# MastModule.net
KiCad netlist of a schematic drawn in EAGLE
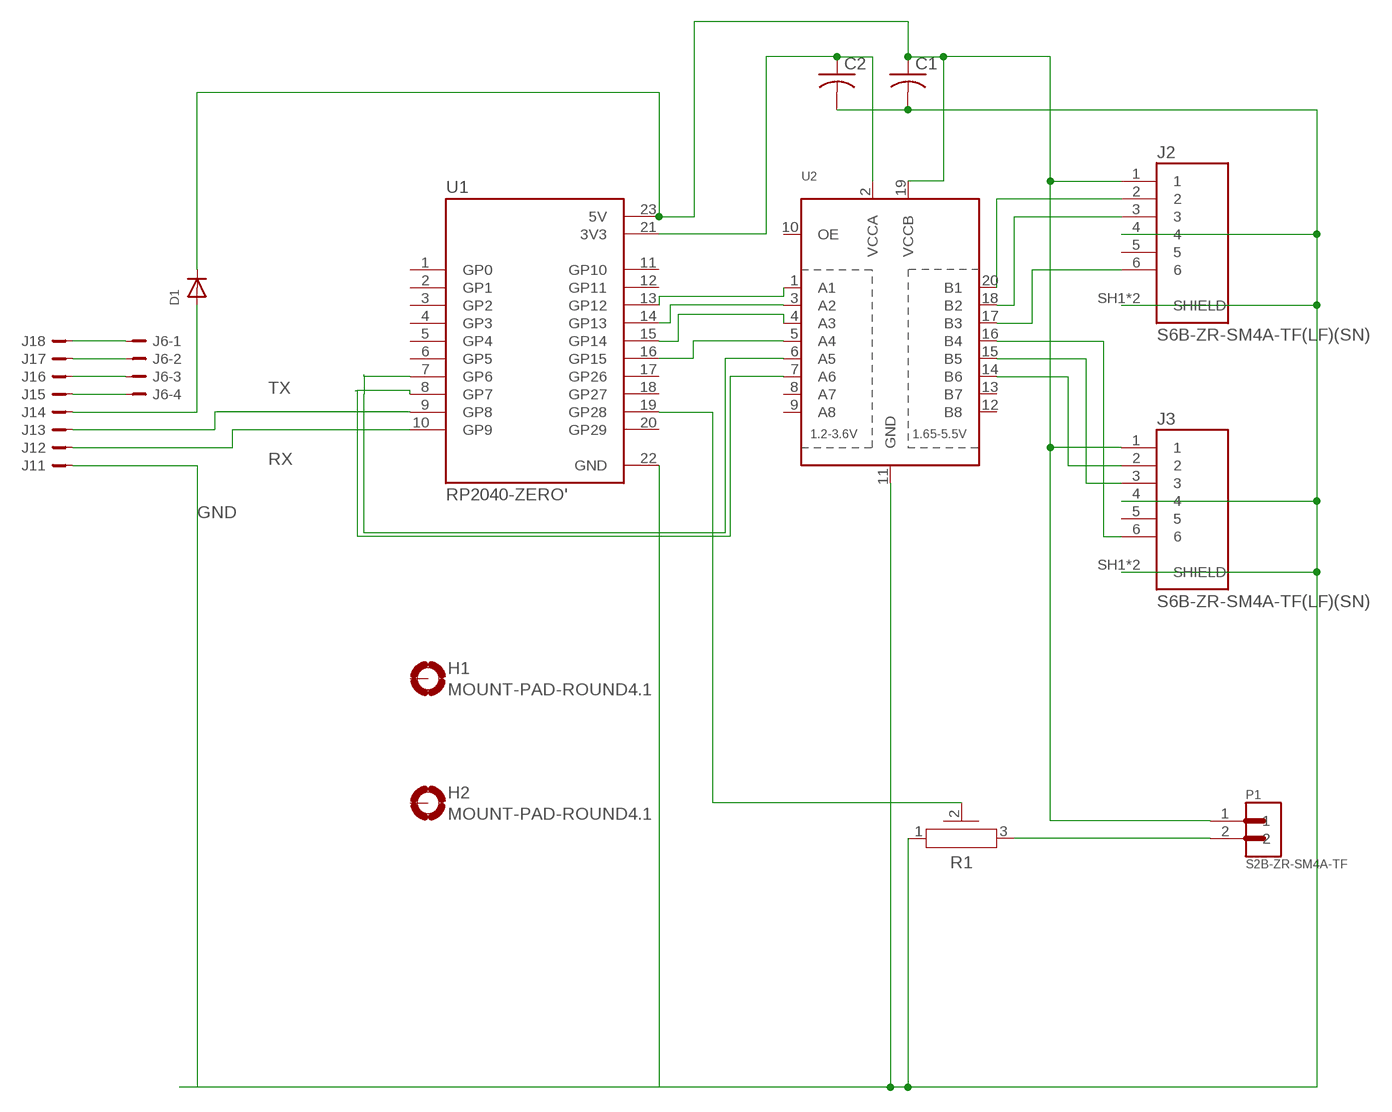
[diagram p0: schematic, sheet 1]

(export (version "E")
  (design (tool "Eeschema 10.0.6"))
  (components
    (comp (ref "C1")
      (value "C-USC1210")
      (footprint "eagle-import:C1210")
      (libsource (lib "eagle-import") (part "C-USC1210"))
    )
    (comp (ref "C2")
      (value "C-USC1210")
      (footprint "eagle-import:C1210")
      (libsource (lib "eagle-import") (part "C-USC1210"))
    )
    (comp (ref "D1")
      (value "DIODESMA")
      (footprint "eagle-import:SMADIODE")
      (libsource (lib "eagle-import") (part "DIODESMA"))
    )
    (comp (ref "H1")
      (value "MOUNT-PAD-ROUND4.1")
      (footprint "eagle-import:4,1-PAD")
      (libsource (lib "eagle-import") (part "MOUNT-PAD-ROUND4.1"))
    )
    (comp (ref "H2")
      (value "MOUNT-PAD-ROUND4.1")
      (footprint "eagle-import:4,1-PAD")
      (libsource (lib "eagle-import") (part "MOUNT-PAD-ROUND4.1"))
    )
    (comp (ref "J1")
      (value "B8B-PH-K-S")
      (footprint "eagle-import:B8B-PH-K-S")
      (libsource (lib "eagle-import") (part "B8B-PH-K-S"))
    )
    (comp (ref "J2")
      (value "S6B-ZR-SM4A-TF(LF)(SN)")
      (footprint "eagle-import:JST_S6B-ZR-SM4A-TF(LF)(SN)")
      (fields (field (name "MF") "JST Sales America Inc."))
      (libsource (lib "eagle-import") (part "S6B-ZR-SM4A-TF(LF)(SN)"))
    )
    (comp (ref "J3")
      (value "S6B-ZR-SM4A-TF(LF)(SN)")
      (footprint "eagle-import:JST_S6B-ZR-SM4A-TF(LF)(SN)")
      (fields (field (name "MF") "JST Sales America Inc."))
      (libsource (lib "eagle-import") (part "S6B-ZR-SM4A-TF(LF)(SN)"))
    )
    (comp (ref "J6")
      (value "JST-PH-4_TH-RA")
      (footprint "eagle-import:S4B-PH-KL")
      (fields (field (name "MF") "JST") (field (name "MPN") "S4B-PH-KL"))
      (libsource (lib "eagle-import") (part "JST-PH-4_TH-RA"))
    )
    (comp (ref "P1")
      (value "S2B-ZR-SM4A-TF")
      (footprint "eagle-import:JST_S2B-ZR-SM4A-TF")
      (fields (field (name "MF") "JST Sales"))
      (libsource (lib "eagle-import") (part "S2B-ZR-SM4A-TF"))
    )
    (comp (ref "R1")
      (value "PV36X")
      (footprint "eagle-import:PV36X")
      (fields
        (field (name "MANUFACTURER") "Bourns Inc.")
        (field (name "MPN") "PV36Xx")
        (field (name "TOLERANCE") "±10%")
      )
      (libsource (lib "eagle-import") (part "PV36X"))
    )
    (comp (ref "U1")
      (value "RP2040-ZERO'")
      (footprint "eagle-import:MODULE_RP2040-ZERO")
      (fields (field (name "MF") "Waveshare Electronics") (field (name "MP") "RP2040-ZERO"))
      (libsource (lib "eagle-import") (part "RP2040-ZERO'"))
    )
    (comp (ref "U2")
      (value "TXB0108PWR")
      (footprint "eagle-import:TSSOP20")
      (libsource (lib "eagle-import") (part "TXB0108PWR"))
    )
  )
  (nets
    (net (code "1") (name "/GND") (class "Default")
      (node (ref "C1") (pin "2") (pinfunction "2_2") (pintype "passive"))
      (node (ref "C2") (pin "2") (pinfunction "2_2") (pintype "passive"))
      (node (ref "J1") (pin "1") (pinfunction "1_1") (pintype "passive"))
      (node (ref "J2") (pin "4") (pinfunction "4_4") (pintype "passive"))
      (node (ref "J2") (pin "SH1") (pinfunction "SHIELD_SH1") (pintype "passive"))
      (node (ref "J2") (pin "SH2") (pinfunction "SHIELD_SH2") (pintype "passive"))
      (node (ref "J3") (pin "4") (pinfunction "4_4") (pintype "passive"))
      (node (ref "J3") (pin "SH1") (pinfunction "SHIELD_SH1") (pintype "passive"))
      (node (ref "J3") (pin "SH2") (pinfunction "SHIELD_SH2") (pintype "passive"))
      (node (ref "R1") (pin "1") (pinfunction "P$1_1") (pintype "passive"))
      (node (ref "U1") (pin "22") (pinfunction "GND_22") (pintype "power_in"))
      (node (ref "U2") (pin "11") (pinfunction "GND_11") (pintype "bidirectional"))
    )
    (net (code "2") (name "/RX") (class "Default")
      (node (ref "J1") (pin "2") (pinfunction "1_2") (pintype "passive"))
      (node (ref "U1") (pin "10") (pinfunction "GP9_10") (pintype "bidirectional"))
    )
    (net (code "3") (name "/TX") (class "Default")
      (node (ref "J1") (pin "3") (pinfunction "1_3") (pintype "passive"))
      (node (ref "U1") (pin "9") (pinfunction "GP8_9") (pintype "bidirectional"))
    )
    (net (code "4") (name "Net-(J1D-1)") (class "Default")
      (node (ref "D1") (pin "A") (pinfunction "A_A") (pintype "passive"))
      (node (ref "J1") (pin "4") (pinfunction "1_4") (pintype "passive"))
    )
    (net (code "5") (name "Net-(J1E-1)") (class "Default")
      (node (ref "J1") (pin "5") (pinfunction "1_5") (pintype "passive"))
      (node (ref "J6") (pin "4") (pinfunction "1_4") (pintype "passive"))
    )
    (net (code "6") (name "Net-(J1F-1)") (class "Default")
      (node (ref "J1") (pin "6") (pinfunction "1_6") (pintype "passive"))
      (node (ref "J6") (pin "3") (pinfunction "1_3") (pintype "passive"))
    )
    (net (code "7") (name "Net-(J1G-1)") (class "Default")
      (node (ref "J1") (pin "7") (pinfunction "1_7") (pintype "passive"))
      (node (ref "J6") (pin "2") (pinfunction "1_2") (pintype "passive"))
    )
    (net (code "8") (name "Net-(J1H-1)") (class "Default")
      (node (ref "J1") (pin "8") (pinfunction "1_8") (pintype "passive"))
      (node (ref "J6") (pin "1") (pinfunction "1_1") (pintype "passive"))
    )
    (net (code "9") (name "Net-(R1-P$2)") (class "Default")
      (node (ref "R1") (pin "2") (pinfunction "P$2_2") (pintype "passive"))
      (node (ref "U1") (pin "19") (pinfunction "GP28_19") (pintype "bidirectional"))
    )
    (net (code "10") (name "Net-(R1-P$3)") (class "Default")
      (node (ref "P1") (pin "2") (pinfunction "2_2") (pintype "passive"))
      (node (ref "R1") (pin "3") (pinfunction "P$3_3") (pintype "passive"))
    )
    (net (code "11") (name "Net-(U1-3V3)") (class "Default")
      (node (ref "C2") (pin "1") (pinfunction "1_1") (pintype "passive"))
      (node (ref "U1") (pin "21") (pinfunction "3V3_21") (pintype "power_in"))
      (node (ref "U2") (pin "2") (pinfunction "VCCA_2") (pintype "bidirectional"))
    )
    (net (code "12") (name "Net-(U1-5V)") (class "Default")
      (node (ref "C1") (pin "1") (pinfunction "1_1") (pintype "passive"))
      (node (ref "D1") (pin "C") (pinfunction "C_C") (pintype "passive"))
      (node (ref "J2") (pin "1") (pinfunction "1_1") (pintype "passive"))
      (node (ref "J3") (pin "1") (pinfunction "1_1") (pintype "passive"))
      (node (ref "P1") (pin "1") (pinfunction "1_1") (pintype "passive"))
      (node (ref "U1") (pin "23") (pinfunction "5V_23") (pintype "power_in"))
      (node (ref "U2") (pin "19") (pinfunction "VCCB_19") (pintype "bidirectional"))
    )
    (net (code "13") (name "Net-(U1-GP6)") (class "Default")
      (node (ref "U1") (pin "7") (pinfunction "GP6_7") (pintype "bidirectional"))
      (node (ref "U2") (pin "6") (pinfunction "A5_6") (pintype "bidirectional"))
    )
    (net (code "14") (name "Net-(U1-GP7)") (class "Default")
      (node (ref "U1") (pin "8") (pinfunction "GP7_8") (pintype "bidirectional"))
      (node (ref "U2") (pin "7") (pinfunction "A6_7") (pintype "bidirectional"))
    )
    (net (code "15") (name "Net-(U1-GP12)") (class "Default")
      (node (ref "U1") (pin "13") (pinfunction "GP12_13") (pintype "bidirectional"))
      (node (ref "U2") (pin "1") (pinfunction "A1_1") (pintype "bidirectional"))
    )
    (net (code "16") (name "Net-(U1-GP13)") (class "Default")
      (node (ref "U1") (pin "14") (pinfunction "GP13_14") (pintype "bidirectional"))
      (node (ref "U2") (pin "3") (pinfunction "A2_3") (pintype "bidirectional"))
    )
    (net (code "17") (name "Net-(U1-GP14)") (class "Default")
      (node (ref "U1") (pin "15") (pinfunction "GP14_15") (pintype "bidirectional"))
      (node (ref "U2") (pin "4") (pinfunction "A3_4") (pintype "bidirectional"))
    )
    (net (code "18") (name "Net-(U1-GP15)") (class "Default")
      (node (ref "U1") (pin "16") (pinfunction "GP15_16") (pintype "bidirectional"))
      (node (ref "U2") (pin "5") (pinfunction "A4_5") (pintype "bidirectional"))
    )
    (net (code "19") (name "Net-(U2-B1)") (class "Default")
      (node (ref "J2") (pin "2") (pinfunction "2_2") (pintype "passive"))
      (node (ref "U2") (pin "20") (pinfunction "B1_20") (pintype "bidirectional"))
    )
    (net (code "20") (name "Net-(U2-B2)") (class "Default")
      (node (ref "J2") (pin "3") (pinfunction "3_3") (pintype "passive"))
      (node (ref "U2") (pin "18") (pinfunction "B2_18") (pintype "bidirectional"))
    )
    (net (code "21") (name "Net-(U2-B3)") (class "Default")
      (node (ref "J2") (pin "6") (pinfunction "6_6") (pintype "passive"))
      (node (ref "U2") (pin "17") (pinfunction "B3_17") (pintype "bidirectional"))
    )
    (net (code "22") (name "Net-(U2-B4)") (class "Default")
      (node (ref "J3") (pin "6") (pinfunction "6_6") (pintype "passive"))
      (node (ref "U2") (pin "16") (pinfunction "B4_16") (pintype "bidirectional"))
    )
    (net (code "23") (name "Net-(U2-B5)") (class "Default")
      (node (ref "J3") (pin "3") (pinfunction "3_3") (pintype "passive"))
      (node (ref "U2") (pin "15") (pinfunction "B5_15") (pintype "bidirectional"))
    )
    (net (code "24") (name "Net-(U2-B6)") (class "Default")
      (node (ref "J3") (pin "2") (pinfunction "2_2") (pintype "passive"))
      (node (ref "U2") (pin "14") (pinfunction "B6_14") (pintype "bidirectional"))
    )
    (net (code "25") (name "unconnected-(H1-MOUNT-PadB4,1)") (class "Default")
      (node (ref "H1") (pin "B4,1") (pinfunction "MOUNT_B4,1") (pintype "passive"))
    )
    (net (code "26") (name "unconnected-(H2-MOUNT-PadB4,1)") (class "Default")
      (node (ref "H2") (pin "B4,1") (pinfunction "MOUNT_B4,1") (pintype "passive"))
    )
    (net (code "27") (name "unconnected-(J2-Pad5)") (class "Default")
      (node (ref "J2") (pin "5") (pinfunction "5_5") (pintype "passive"))
    )
    (net (code "28") (name "unconnected-(J3-Pad5)") (class "Default")
      (node (ref "J3") (pin "5") (pinfunction "5_5") (pintype "passive"))
    )
    (net (code "29") (name "unconnected-(U1-GP0-Pad1)") (class "Default")
      (node (ref "U1") (pin "1") (pinfunction "GP0_1") (pintype "bidirectional"))
    )
    (net (code "30") (name "unconnected-(U1-GP1-Pad2)") (class "Default")
      (node (ref "U1") (pin "2") (pinfunction "GP1_2") (pintype "bidirectional"))
    )
    (net (code "31") (name "unconnected-(U1-GP2-Pad3)") (class "Default")
      (node (ref "U1") (pin "3") (pinfunction "GP2_3") (pintype "bidirectional"))
    )
    (net (code "32") (name "unconnected-(U1-GP3-Pad4)") (class "Default")
      (node (ref "U1") (pin "4") (pinfunction "GP3_4") (pintype "bidirectional"))
    )
    (net (code "33") (name "unconnected-(U1-GP4-Pad5)") (class "Default")
      (node (ref "U1") (pin "5") (pinfunction "GP4_5") (pintype "bidirectional"))
    )
    (net (code "34") (name "unconnected-(U1-GP5-Pad6)") (class "Default")
      (node (ref "U1") (pin "6") (pinfunction "GP5_6") (pintype "bidirectional"))
    )
    (net (code "35") (name "unconnected-(U1-GP10-Pad11)") (class "Default")
      (node (ref "U1") (pin "11") (pinfunction "GP10_11") (pintype "bidirectional"))
    )
    (net (code "36") (name "unconnected-(U1-GP11-Pad12)") (class "Default")
      (node (ref "U1") (pin "12") (pinfunction "GP11_12") (pintype "bidirectional"))
    )
    (net (code "37") (name "unconnected-(U1-GP26-Pad17)") (class "Default")
      (node (ref "U1") (pin "17") (pinfunction "GP26_17") (pintype "bidirectional"))
    )
    (net (code "38") (name "unconnected-(U1-GP27-Pad18)") (class "Default")
      (node (ref "U1") (pin "18") (pinfunction "GP27_18") (pintype "bidirectional"))
    )
    (net (code "39") (name "unconnected-(U1-GP29-Pad20)") (class "Default")
      (node (ref "U1") (pin "20") (pinfunction "GP29_20") (pintype "bidirectional"))
    )
    (net (code "40") (name "unconnected-(U2-A7-Pad8)") (class "Default")
      (node (ref "U2") (pin "8") (pinfunction "A7_8") (pintype "bidirectional"))
    )
    (net (code "41") (name "unconnected-(U2-A8-Pad9)") (class "Default")
      (node (ref "U2") (pin "9") (pinfunction "A8_9") (pintype "bidirectional"))
    )
    (net (code "42") (name "unconnected-(U2-B7-Pad13)") (class "Default")
      (node (ref "U2") (pin "13") (pinfunction "B7_13") (pintype "bidirectional"))
    )
    (net (code "43") (name "unconnected-(U2-B8-Pad12)") (class "Default")
      (node (ref "U2") (pin "12") (pinfunction "B8_12") (pintype "bidirectional"))
    )
    (net (code "44") (name "unconnected-(U2-OE-Pad10)") (class "Default")
      (node (ref "U2") (pin "10") (pinfunction "OE_10") (pintype "bidirectional"))
    )
  )
)
